# Qwiic_Distance_Sensor_-_VL53L1X.net
KiCad netlist of a schematic drawn in EAGLE
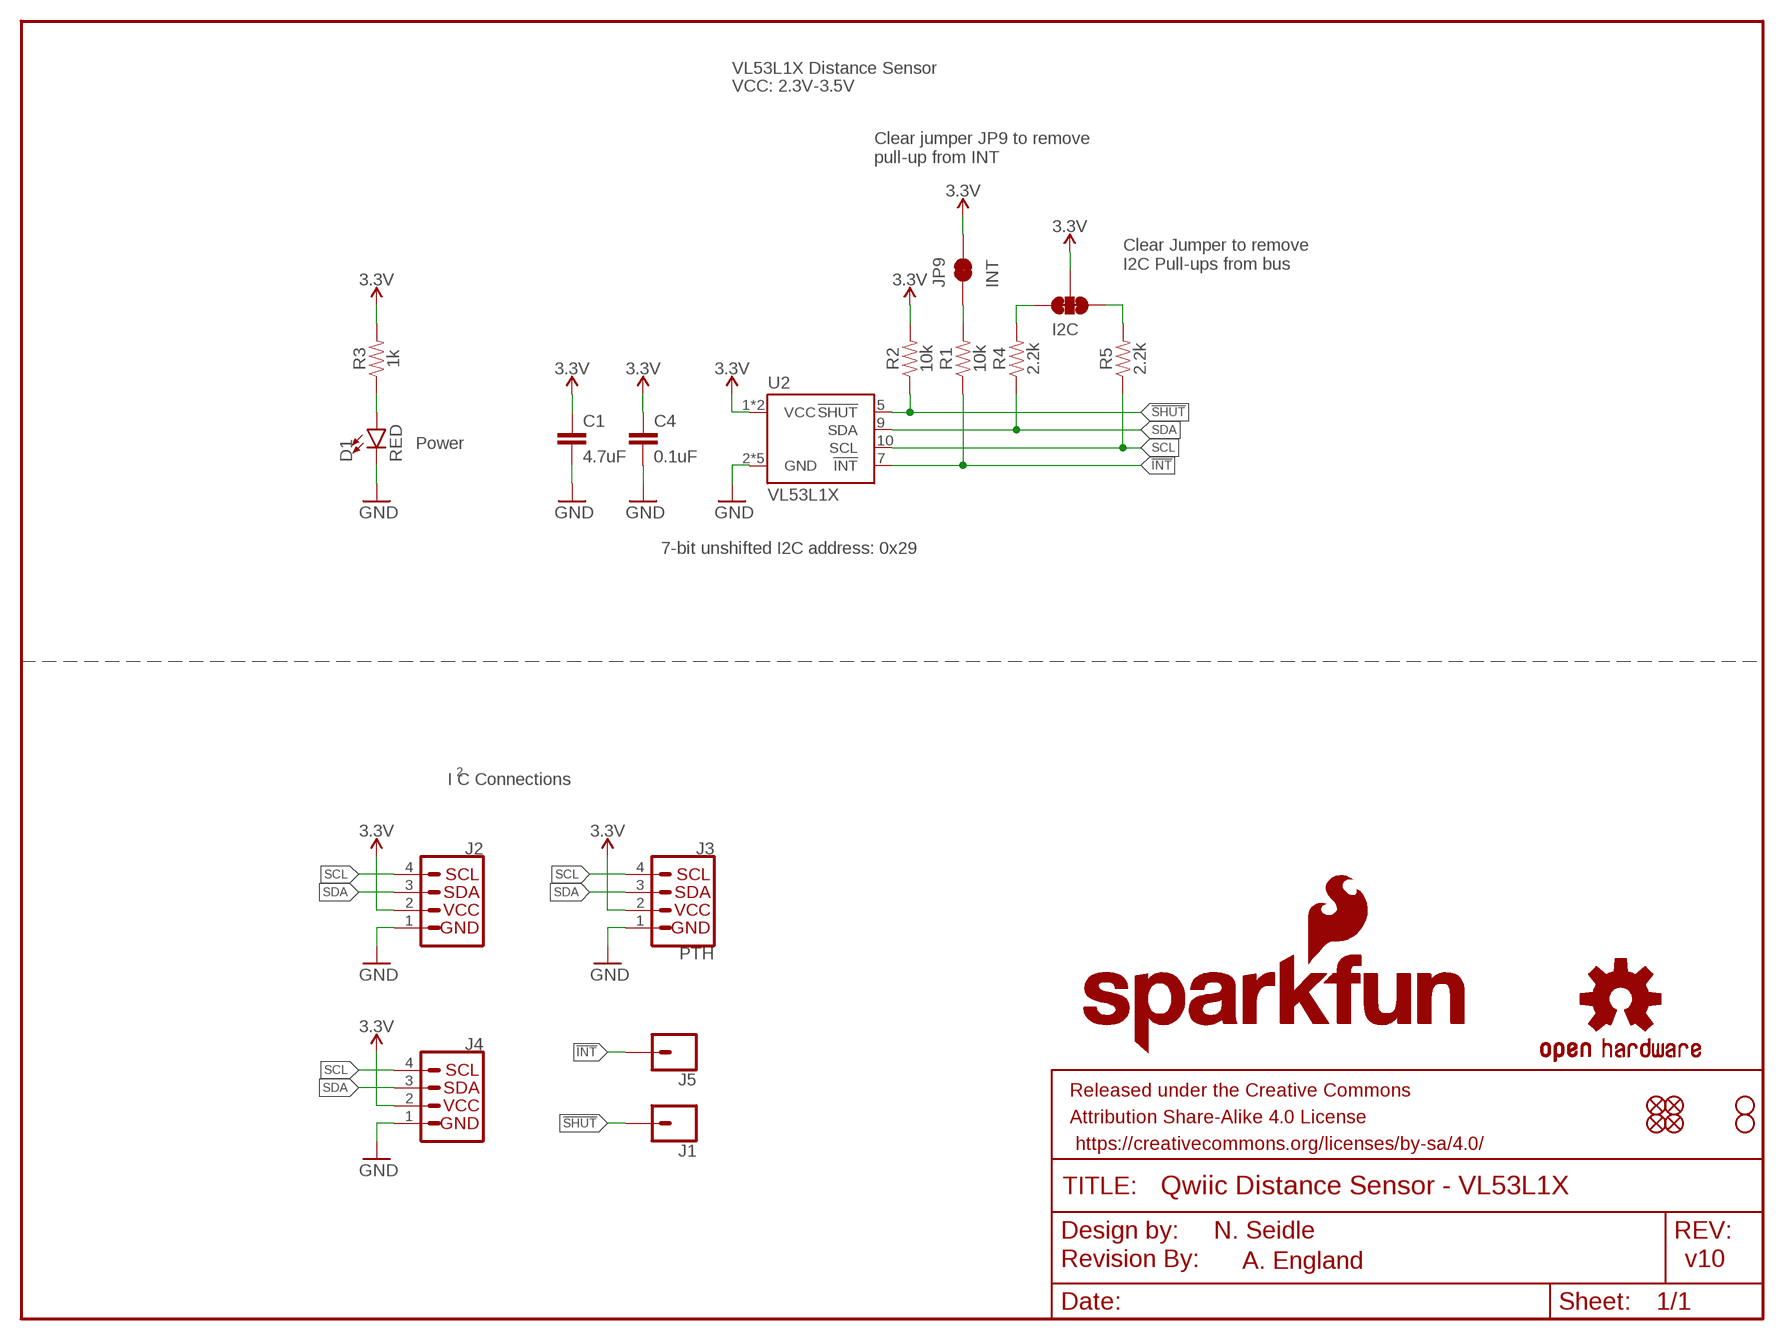
[diagram p0: schematic, sheet 1]

(export (version "E")
  (design (tool "Eeschema 10.0.6"))
  (components
    (comp (ref "C1")
      (value "4.7uF")
      (footprint "eagle-import:0603")
      (libsource (lib "eagle-import") (part "4.7UF0603"))
    )
    (comp (ref "C4")
      (value "0.1uF")
      (footprint "eagle-import:0603")
      (libsource (lib "eagle-import") (part "0.1UF-0603-25V-(+80/-20%)"))
    )
    (comp (ref "D1")
      (value "RED")
      (footprint "eagle-import:LED-0603")
      (libsource (lib "eagle-import") (part "LED-RED0603"))
    )
    (comp (ref "FRAME1")
      (value "FRAME-LETTER")
      (footprint "eagle-import:CREATIVE_COMMONS")
      (libsource (lib "eagle-import") (part "FRAME-LETTER"))
    )
    (comp (ref "I2C")
      (value "JUMPER-SMT_3_2-NC_TRACE_SILK")
      (footprint "eagle-import:SMT-JUMPER_3_2-NC_TRACE_SILK")
      (libsource (lib "eagle-import") (part "JUMPER-SMT_3_2-NC_TRACE_SILK"))
    )
    (comp (ref "J1")
      (value "CONN_01PTH_NO_SILK_YES_STOP")
      (footprint "eagle-import:1X01_NO_SILK")
      (libsource (lib "eagle-import") (part "CONN_01PTH_NO_SILK_YES_STOP"))
    )
    (comp (ref "J2")
      (value "QWIIC_CONNECTORJS-1MM")
      (footprint "eagle-import:1X04_1MM_RA")
      (libsource (lib "eagle-import") (part "QWIIC_CONNECTORJS-1MM"))
    )
    (comp (ref "J3")
      (value "PTH")
      (footprint "eagle-import:1X04_NO_SILK")
      (libsource (lib "eagle-import") (part "I2C_STANDARD_NO_SILK"))
    )
    (comp (ref "J4")
      (value "QWIIC_CONNECTORJS-1MM")
      (footprint "eagle-import:1X04_1MM_RA")
      (libsource (lib "eagle-import") (part "QWIIC_CONNECTORJS-1MM"))
    )
    (comp (ref "J5")
      (value "CONN_01PTH_NO_SILK_YES_STOP")
      (footprint "eagle-import:1X01_NO_SILK")
      (libsource (lib "eagle-import") (part "CONN_01PTH_NO_SILK_YES_STOP"))
    )
    (comp (ref "JP1")
      (value "FIDUCIALUFIDUCIAL")
      (footprint "eagle-import:MICRO-FIDUCIAL")
      (libsource (lib "eagle-import") (part "FIDUCIALUFIDUCIAL"))
    )
    (comp (ref "JP2")
      (value "FIDUCIALUFIDUCIAL")
      (footprint "eagle-import:MICRO-FIDUCIAL")
      (libsource (lib "eagle-import") (part "FIDUCIALUFIDUCIAL"))
    )
    (comp (ref "JP3")
      (value "STAND-OFF")
      (footprint "eagle-import:STAND-OFF")
      (libsource (lib "eagle-import") (part "STAND-OFF"))
    )
    (comp (ref "JP4")
      (value "STAND-OFF")
      (footprint "eagle-import:STAND-OFF")
      (libsource (lib "eagle-import") (part "STAND-OFF"))
    )
    (comp (ref "JP5")
      (value "FIDUCIALUFIDUCIAL")
      (footprint "eagle-import:MICRO-FIDUCIAL")
      (libsource (lib "eagle-import") (part "FIDUCIALUFIDUCIAL"))
    )
    (comp (ref "JP6")
      (value "FIDUCIALUFIDUCIAL")
      (footprint "eagle-import:MICRO-FIDUCIAL")
      (libsource (lib "eagle-import") (part "FIDUCIALUFIDUCIAL"))
    )
    (comp (ref "JP9")
      (value "INT")
      (footprint "eagle-import:PAD-JUMPER-2-NC_BY_TRACE_YES_SILK")
      (libsource (lib "eagle-import") (part "JUMPER-PAD-2-NC_BY_TRACE"))
    )
    (comp (ref "LOGO1")
      (value "OSHW-LOGOMINI")
      (footprint "eagle-import:OSHW-LOGO-MINI")
      (libsource (lib "eagle-import") (part "OSHW-LOGOMINI"))
    )
    (comp (ref "LOGO2")
      (value "REVISION")
      (footprint "eagle-import:REVISION")
      (libsource (lib "eagle-import") (part "REVISION"))
    )
    (comp (ref "R1")
      (value "10k")
      (footprint "eagle-import:0603")
      (libsource (lib "eagle-import") (part "10KOHM-0603-1/10W-1%"))
    )
    (comp (ref "R2")
      (value "10k")
      (footprint "eagle-import:0603")
      (libsource (lib "eagle-import") (part "10KOHM-0603-1/10W-1%"))
    )
    (comp (ref "R3")
      (value "1k")
      (footprint "eagle-import:0603")
      (libsource (lib "eagle-import") (part "1KOHM-0603-1/10W-1%"))
    )
    (comp (ref "R4")
      (value "2.2k")
      (footprint "eagle-import:0603")
      (libsource (lib "eagle-import") (part "2.2KOHM-0603-1/10W-1%"))
    )
    (comp (ref "R5")
      (value "2.2k")
      (footprint "eagle-import:0603")
      (libsource (lib "eagle-import") (part "2.2KOHM-0603-1/10W-1%"))
    )
    (comp (ref "U$1")
      (value "SFE_LOGO_NAME.1_INCH")
      (footprint "eagle-import:SFE_LOGO_NAME_.1")
      (libsource (lib "eagle-import") (part "SFE_LOGO_NAME.1_INCH"))
    )
    (comp (ref "U$2")
      (value "SFE_LOGO_NAME_FLAME.1_INCH")
      (footprint "eagle-import:SFE_LOGO_NAME_FLAME_.1")
      (libsource (lib "eagle-import") (part "SFE_LOGO_NAME_FLAME.1_INCH"))
    )
    (comp (ref "U2")
      (value "VL53L1X")
      (footprint "eagle-import:VL53L1X")
      (libsource (lib "eagle-import") (part "VL53L1XSMD"))
    )
  )
  (nets
    (net (code "1") (name "/~{INT}") (class "Default")
      (node (ref "J5") (pin "1") (pinfunction "1_1") (pintype "passive"))
      (node (ref "R1") (pin "1") (pinfunction "1_1") (pintype "passive"))
      (node (ref "U2") (pin "7") (pinfunction "~{INT}_7") (pintype "bidirectional"))
    )
    (net (code "2") (name "/~{SHUT}") (class "Default")
      (node (ref "J1") (pin "1") (pinfunction "1_1") (pintype "passive"))
      (node (ref "R2") (pin "1") (pinfunction "1_1") (pintype "passive"))
      (node (ref "U2") (pin "5") (pinfunction "~{SHUT}_5") (pintype "bidirectional"))
    )
    (net (code "3") (name "3.3V") (class "Default")
      (node (ref "C1") (pin "1") (pinfunction "1_1") (pintype "passive"))
      (node (ref "C4") (pin "1") (pinfunction "1_1") (pintype "passive"))
      (node (ref "I2C") (pin "2") (pinfunction "2_2") (pintype "passive"))
      (node (ref "J2") (pin "2") (pinfunction "2_2") (pintype "power_in"))
      (node (ref "J3") (pin "2") (pinfunction "VCC_2") (pintype "power_in"))
      (node (ref "J4") (pin "2") (pinfunction "2_2") (pintype "power_in"))
      (node (ref "JP9") (pin "2") (pinfunction "2_2") (pintype "passive"))
      (node (ref "R2") (pin "2") (pinfunction "2_2") (pintype "passive"))
      (node (ref "R3") (pin "2") (pinfunction "2_2") (pintype "passive"))
      (node (ref "U2") (pin "1") (pinfunction "VCC_1") (pintype "bidirectional"))
      (node (ref "U2") (pin "11") (pinfunction "VCC_11") (pintype "bidirectional"))
    )
    (net (code "4") (name "GND") (class "Default")
      (node (ref "C1") (pin "2") (pinfunction "2_2") (pintype "passive"))
      (node (ref "C4") (pin "2") (pinfunction "2_2") (pintype "passive"))
      (node (ref "D1") (pin "C") (pinfunction "C_C") (pintype "passive"))
      (node (ref "J2") (pin "1") (pinfunction "1_1") (pintype "power_in"))
      (node (ref "J3") (pin "1") (pinfunction "GND_1") (pintype "power_in"))
      (node (ref "J4") (pin "1") (pinfunction "1_1") (pintype "power_in"))
      (node (ref "U2") (pin "12") (pinfunction "GND_12") (pintype "bidirectional"))
      (node (ref "U2") (pin "2") (pinfunction "GND_2") (pintype "bidirectional"))
      (node (ref "U2") (pin "3") (pinfunction "GND_3") (pintype "bidirectional"))
      (node (ref "U2") (pin "4") (pinfunction "GND_4") (pintype "bidirectional"))
      (node (ref "U2") (pin "6") (pinfunction "GND_6") (pintype "bidirectional"))
    )
    (net (code "5") (name "Net-(D1-PadA)") (class "Default")
      (node (ref "D1") (pin "A") (pinfunction "A_A") (pintype "passive"))
      (node (ref "R3") (pin "1") (pinfunction "1_1") (pintype "passive"))
    )
    (net (code "6") (name "Net-(I2C-Pad1)") (class "Default")
      (node (ref "I2C") (pin "1") (pinfunction "1_1") (pintype "passive"))
      (node (ref "R5") (pin "2") (pinfunction "2_2") (pintype "passive"))
    )
    (net (code "7") (name "Net-(I2C-Pad3)") (class "Default")
      (node (ref "I2C") (pin "3") (pinfunction "3_3") (pintype "passive"))
      (node (ref "R4") (pin "2") (pinfunction "2_2") (pintype "passive"))
    )
    (net (code "8") (name "Net-(JP9-Pad1)") (class "Default")
      (node (ref "JP9") (pin "1") (pinfunction "1_1") (pintype "passive"))
      (node (ref "R1") (pin "2") (pinfunction "2_2") (pintype "passive"))
    )
    (net (code "9") (name "SCL") (class "Default")
      (node (ref "J2") (pin "4") (pinfunction "4_4") (pintype "passive"))
      (node (ref "J3") (pin "4") (pinfunction "SCL_4") (pintype "passive"))
      (node (ref "J4") (pin "4") (pinfunction "4_4") (pintype "passive"))
      (node (ref "R5") (pin "1") (pinfunction "1_1") (pintype "passive"))
      (node (ref "U2") (pin "10") (pinfunction "SCL_10") (pintype "bidirectional"))
    )
    (net (code "10") (name "SDA") (class "Default")
      (node (ref "J2") (pin "3") (pinfunction "3_3") (pintype "passive"))
      (node (ref "J3") (pin "3") (pinfunction "SDA_3") (pintype "passive"))
      (node (ref "J4") (pin "3") (pinfunction "3_3") (pintype "passive"))
      (node (ref "R4") (pin "1") (pinfunction "1_1") (pintype "passive"))
      (node (ref "U2") (pin "9") (pinfunction "SDA_9") (pintype "bidirectional"))
    )
  )
)
